# 11-DisplayPort.net
KiCad netlist of a schematic drawn in Altium Designer
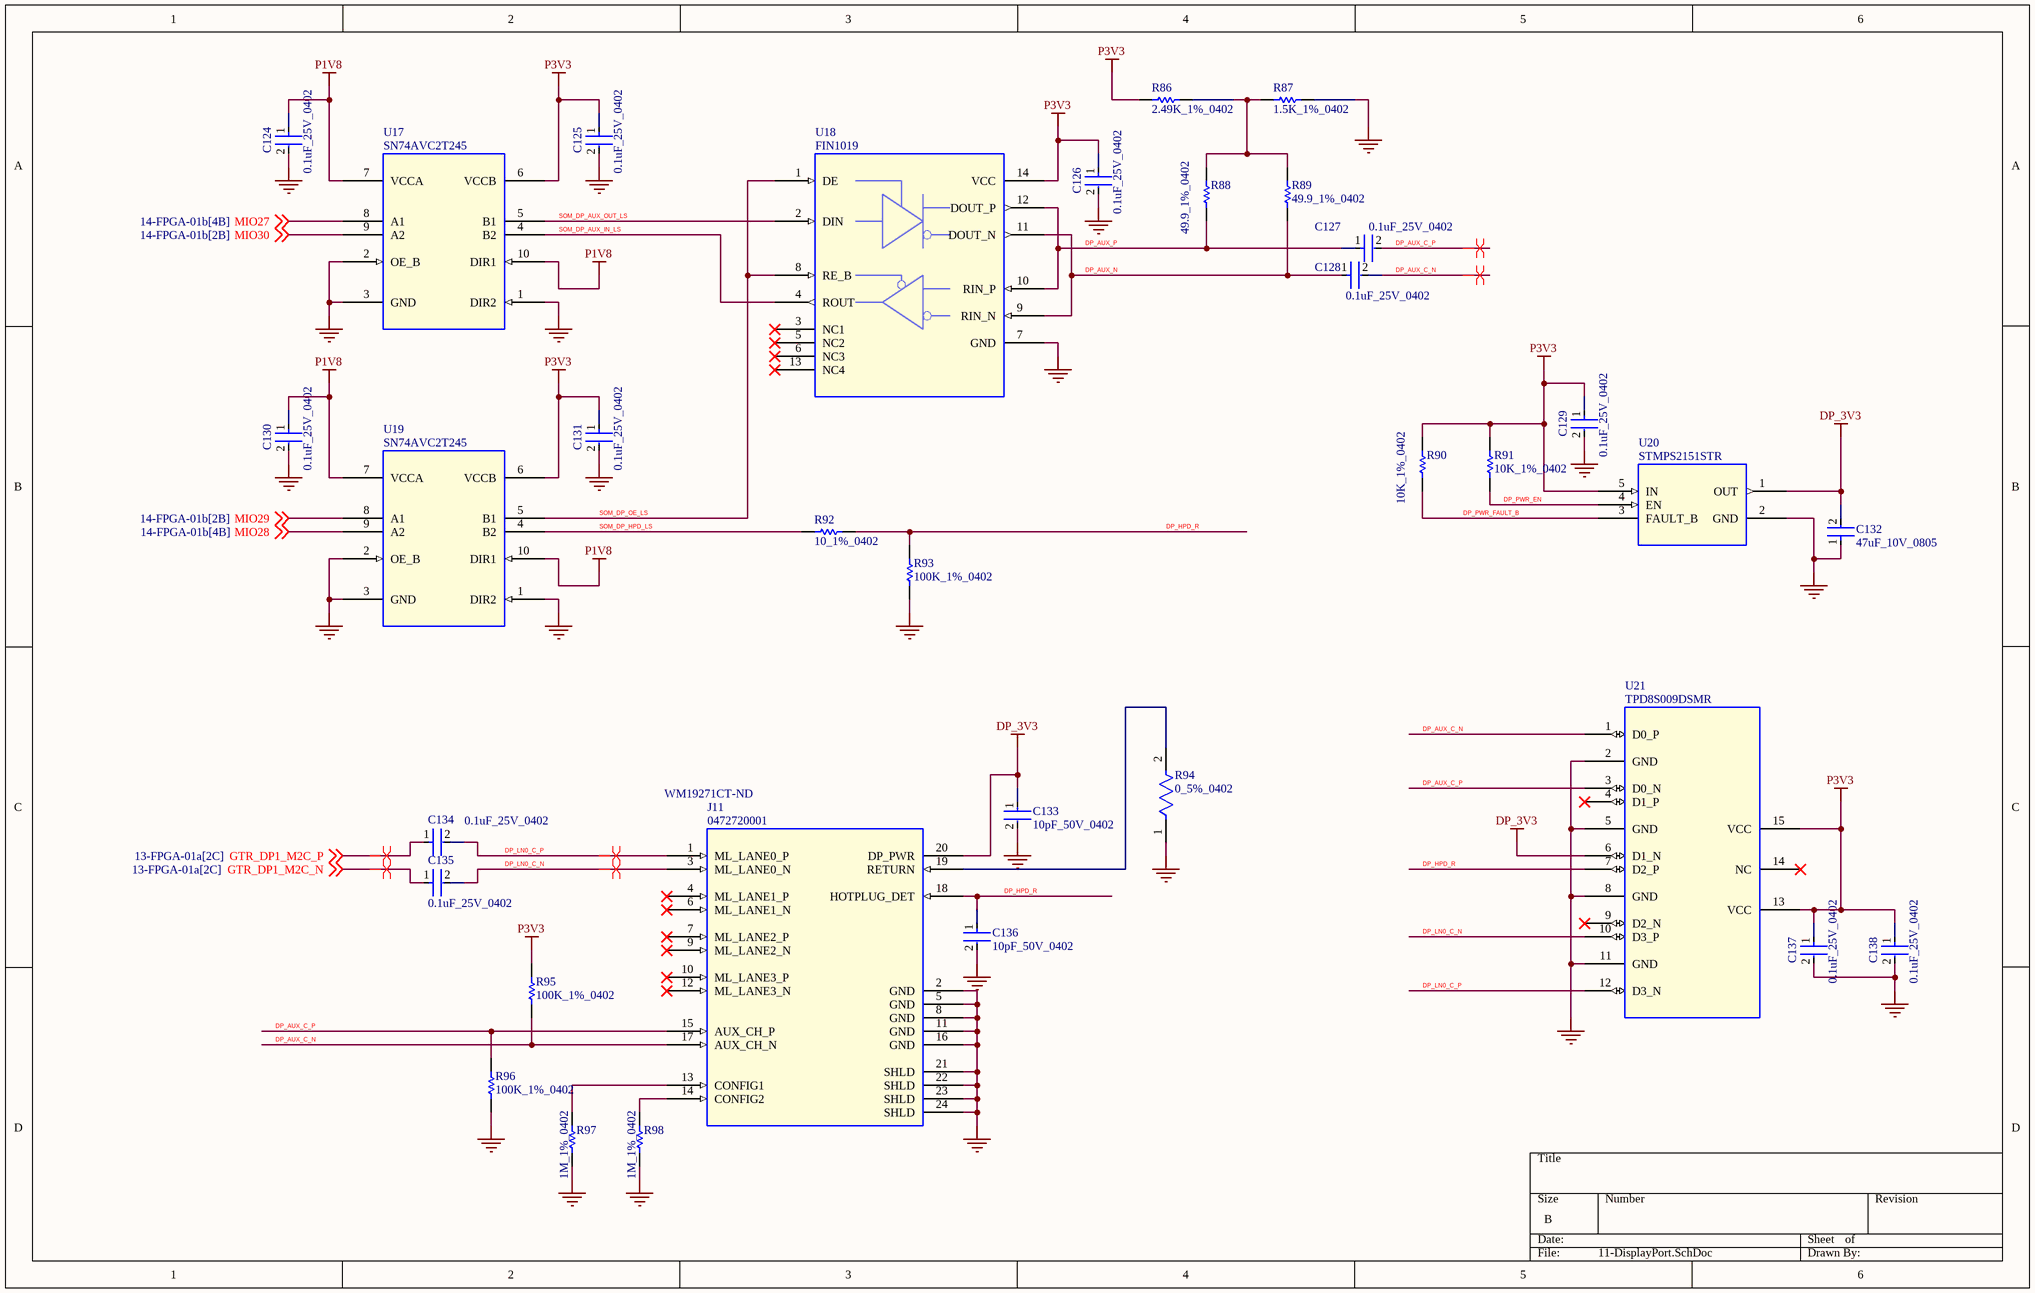
[diagram p0: 11-DisplayPort.SchDoc]

(export (version "E")
  (design (tool "Eeschema 10.0.6"))
  (components
    (comp (ref "C124")
      (value "0.1uF_25V_0402")
      (footprint "FP-0402-L_1_0_1-W_0_5_0_1-IPC_C")
      (description "General Purpose Ceramic Capacitor, 0402, 100nF, 10%, X7R, 15%, 25V")
      (fields (field (name "VOLTAGE") "25V") (field (name "TOLERANCE") "10%"))
      (libsource (lib "Altium Content Vault") (part "b4654b650e69147ec39a6b967a45e02"))
    )
    (comp (ref "C125")
      (value "0.1uF_25V_0402")
      (footprint "FP-0402-L_1_0_1-W_0_5_0_1-IPC_C")
      (description "General Purpose Ceramic Capacitor, 0402, 100nF, 10%, X7R, 15%, 25V")
      (fields (field (name "VOLTAGE") "25V") (field (name "TOLERANCE") "10%"))
      (libsource (lib "Altium Content Vault") (part "b4654b650e69147ec39a6b967a45e02"))
    )
    (comp (ref "C126")
      (value "0.1uF_25V_0402")
      (footprint "FP-0402-L_1_0_1-W_0_5_0_1-IPC_C")
      (description "General Purpose Ceramic Capacitor, 0402, 100nF, 10%, X7R, 15%, 25V")
      (fields (field (name "VOLTAGE") "25V") (field (name "TOLERANCE") "10%"))
      (libsource (lib "Altium Content Vault") (part "b4654b650e69147ec39a6b967a45e02"))
    )
    (comp (ref "C127")
      (value "0.1uF_25V_0402")
      (footprint "FP-0402-L_1_0_1-W_0_5_0_1-IPC_C")
      (description "General Purpose Ceramic Capacitor, 0402, 100nF, 10%, X7R, 15%, 25V")
      (fields (field (name "VOLTAGE") "25V") (field (name "TOLERANCE") "10%"))
      (libsource (lib "Altium Content Vault") (part "b4654b650e69147ec39a6b967a45e02"))
    )
    (comp (ref "C128")
      (value "0.1uF_25V_0402")
      (footprint "FP-0402-L_1_0_1-W_0_5_0_1-IPC_C")
      (description "General Purpose Ceramic Capacitor, 0402, 100nF, 10%, X7R, 15%, 25V")
      (fields (field (name "VOLTAGE") "25V") (field (name "TOLERANCE") "10%"))
      (libsource (lib "Altium Content Vault") (part "b4654b650e69147ec39a6b967a45e02"))
    )
    (comp (ref "C129")
      (value "0.1uF_25V_0402")
      (footprint "FP-0402-L_1_0_1-W_0_5_0_1-IPC_C")
      (description "General Purpose Ceramic Capacitor, 0402, 100nF, 10%, X7R, 15%, 25V")
      (fields (field (name "VOLTAGE") "25V") (field (name "TOLERANCE") "10%"))
      (libsource (lib "Altium Content Vault") (part "b4654b650e69147ec39a6b967a45e02"))
    )
    (comp (ref "C130")
      (value "0.1uF_25V_0402")
      (footprint "FP-0402-L_1_0_1-W_0_5_0_1-IPC_C")
      (description "General Purpose Ceramic Capacitor, 0402, 100nF, 10%, X7R, 15%, 25V")
      (fields (field (name "VOLTAGE") "25V") (field (name "TOLERANCE") "10%"))
      (libsource (lib "Altium Content Vault") (part "b4654b650e69147ec39a6b967a45e02"))
    )
    (comp (ref "C131")
      (value "0.1uF_25V_0402")
      (footprint "FP-0402-L_1_0_1-W_0_5_0_1-IPC_C")
      (description "General Purpose Ceramic Capacitor, 0402, 100nF, 10%, X7R, 15%, 25V")
      (fields (field (name "VOLTAGE") "25V") (field (name "TOLERANCE") "10%"))
      (libsource (lib "Altium Content Vault") (part "b4654b650e69147ec39a6b967a45e02"))
    )
    (comp (ref "C132")
      (value "47uF_10V_0805")
      (footprint "FP-GRM21B-0_2-e0_2_0_7-IPC_A")
      (description "Chip Multilayer Ceramic Capacitors for General Purpose, 0805, 47uF, X5R, 15%, 20%, 10V")
      (fields (field (name "TOLERANCE") "20%") (field (name "VOLTAGE") "10V"))
      (libsource (lib "Altium Content Vault") (part "b4654b650e69147ec39a6b967a45e02"))
    )
    (comp (ref "C133")
      (value "10pF_50V_0402")
      (footprint "FP-C1005-050-0_05-IPC_C")
      (description "CAP CER 10PF 50V C0G 0402")
      (fields (field (name "VOLTAGE") "50V"))
      (libsource (lib "Altium Content Vault") (part "b4654b650e69147ec39a6b967a45e02"))
    )
    (comp (ref "C134")
      (value "0.1uF_25V_0402")
      (footprint "FP-0402-L_1_0_1-W_0_5_0_1-IPC_C")
      (description "General Purpose Ceramic Capacitor, 0402, 100nF, 10%, X7R, 15%, 25V")
      (fields (field (name "VOLTAGE") "25V") (field (name "TOLERANCE") "10%"))
      (libsource (lib "Altium Content Vault") (part "b4654b650e69147ec39a6b967a45e02"))
    )
    (comp (ref "C135")
      (value "0.1uF_25V_0402")
      (footprint "FP-0402-L_1_0_1-W_0_5_0_1-IPC_C")
      (description "General Purpose Ceramic Capacitor, 0402, 100nF, 10%, X7R, 15%, 25V")
      (fields (field (name "VOLTAGE") "25V") (field (name "TOLERANCE") "10%"))
      (libsource (lib "Altium Content Vault") (part "b4654b650e69147ec39a6b967a45e02"))
    )
    (comp (ref "C136")
      (value "10pF_50V_0402")
      (footprint "FP-C1005-050-0_05-IPC_C")
      (description "CAP CER 10PF 50V C0G 0402")
      (fields (field (name "VOLTAGE") "50V"))
      (libsource (lib "Altium Content Vault") (part "b4654b650e69147ec39a6b967a45e02"))
    )
    (comp (ref "C137")
      (value "0.1uF_25V_0402")
      (footprint "FP-0402-L_1_0_1-W_0_5_0_1-IPC_C")
      (description "General Purpose Ceramic Capacitor, 0402, 100nF, 10%, X7R, 15%, 25V")
      (fields (field (name "VOLTAGE") "25V") (field (name "TOLERANCE") "10%"))
      (libsource (lib "Altium Content Vault") (part "b4654b650e69147ec39a6b967a45e02"))
    )
    (comp (ref "C138")
      (value "0.1uF_25V_0402")
      (footprint "FP-0402-L_1_0_1-W_0_5_0_1-IPC_C")
      (description "General Purpose Ceramic Capacitor, 0402, 100nF, 10%, X7R, 15%, 25V")
      (fields (field (name "VOLTAGE") "25V") (field (name "TOLERANCE") "10%"))
      (libsource (lib "Altium Content Vault") (part "b4654b650e69147ec39a6b967a45e02"))
    )
    (comp (ref "J11")
      (value "0472720001")
      (footprint "CON_MOLEX_47272")
      (description "Conn Rcpt DisplayPort Female RA 20 Pos 0.5mm P Black SMT")
      (fields
        (field (name "AGILE PART NUMBER") "CON-00139-01")
        (field (name "MANUFACTURER") "MOLEX")
        (field (name "SUPPLIER PART NUMBER 1") "WM19271CT-ND")
      )
      (libsource (lib "*") (part "0472720001"))
    )
    (comp (ref "R86")
      (value "2.49K_1%_0402")
      (footprint "RESC1005X40X25ML05T05")
      (fields (field (name "MANUFACTURER") "Vishay Dale") (field (name "PART NUMBER") "CRCW04022K49FKTD"))
      (libsource (lib "Altium Content Vault") (part "RES"))
    )
    (comp (ref "R87")
      (value "1.5K_1%_0402")
      (footprint "RESC1005X40X25NL05T05")
      (fields (field (name "PART NUMBER") "CRCW04021K50FKED") (field (name "MANUFACTURER") "Vishay Dale"))
      (libsource (lib "Altium Content Vault") (part "RES"))
    )
    (comp (ref "R88")
      (value "49.9_1%_0402")
      (footprint "RESC1005X40X25NL10T10")
      (fields (field (name "PART NUMBER") "RK73H1ETTP49R9F") (field (name "MANUFACTURER") "KOA Speer"))
      (libsource (lib "Altium Content Vault") (part "RES"))
    )
    (comp (ref "R89")
      (value "49.9_1%_0402")
      (footprint "RESC1005X40X25NL10T10")
      (fields (field (name "PART NUMBER") "RK73H1ETTP49R9F") (field (name "MANUFACTURER") "KOA Speer"))
      (libsource (lib "Altium Content Vault") (part "RES"))
    )
    (comp (ref "R90")
      (value "10K_1%_0402")
      (footprint "RESC1005X40X25ML05T05")
      (fields (field (name "PART NUMBER") "ERJ-2GEJ103X") (field (name "MANUFACTURER") "Panasonic"))
      (libsource (lib "Altium Content Vault") (part "RES"))
    )
    (comp (ref "R91")
      (value "10K_1%_0402")
      (footprint "RESC1005X40X25ML05T05")
      (fields (field (name "PART NUMBER") "ERJ-2GEJ103X") (field (name "MANUFACTURER") "Panasonic"))
      (libsource (lib "Altium Content Vault") (part "RES"))
    )
    (comp (ref "R92")
      (value "10_1%_0402")
      (footprint "RESC1005X40X25LL10T10")
      (fields (field (name "PART NUMBER") "RK73H1ETTP10R0F") (field (name "MANUFACTURER") "KOA Speer"))
      (libsource (lib "Altium Content Vault") (part "RES"))
    )
    (comp (ref "R93")
      (value "100K_1%_0402")
      (footprint "RESC1005X40X25ML05T05")
      (fields (field (name "PART NUMBER") "CRCW0402100KFKTD") (field (name "MANUFACTURER") "Vishay Dale"))
      (libsource (lib "Altium Content Vault") (part "RES"))
    )
    (comp (ref "R94")
      (value "0_5%_0402")
      (footprint "FP-AC0402-0_37-IPC_B")
      (description "RESISTOR 0402 JUMPER ZERO OHM")
      (fields (field (name "TOLERANCE") "1%"))
      (libsource (lib "Altium Content Vault") (part "1029c3af85768c4190bb7ad29bc67b5"))
    )
    (comp (ref "R95")
      (value "100K_1%_0402")
      (footprint "RESC1005X40X25ML05T05")
      (fields (field (name "PART NUMBER") "CRCW0402100KFKTD") (field (name "MANUFACTURER") "Vishay Dale"))
      (libsource (lib "Altium Content Vault") (part "RES"))
    )
    (comp (ref "R96")
      (value "100K_1%_0402")
      (footprint "RESC1005X40X25ML05T05")
      (fields (field (name "PART NUMBER") "CRCW0402100KFKTD") (field (name "MANUFACTURER") "Vishay Dale"))
      (libsource (lib "Altium Content Vault") (part "RES"))
    )
    (comp (ref "R97")
      (value "1M_1%_0402")
      (footprint "RESC1005X40X25NL10T10")
      (fields
        (field (name "MANUFACTURER") "TE Connectivity / AMP")
        (field (name "PART NUMBER") "CRG0402F1M0")
      )
      (libsource (lib "Altium Content Vault") (part "RES"))
    )
    (comp (ref "R98")
      (value "1M_1%_0402")
      (footprint "RESC1005X40X25NL10T10")
      (fields
        (field (name "MANUFACTURER") "TE Connectivity / AMP")
        (field (name "PART NUMBER") "CRG0402F1M0")
      )
      (libsource (lib "Altium Content Vault") (part "RES"))
    )
    (comp (ref "U17")
      (value "SN74AVC2T245")
      (footprint "QFN40P140X180X55-10")
      (description "IC Lvl Trans 2-Bit Bidir 500Mbps 1.2-3.6V 50mA UQFN-10")
      (fields
        (field (name "AGILE PART NUMBER") "ICS-00048-01")
        (field (name "MANUFACTURER") "TEXAS INSTRUMENTS")
      )
      (libsource (lib "*") (part "SN74AVC2T245"))
    )
    (comp (ref "U18")
      (value "FIN1019")
      (footprint "TSSOP_14")
      (description "IC Lvl Trans LVTTL-LVDS Diff 400Mbps 3.3V 2.5nSec TSSOP-14")
      (fields (field (name "AGILE PART NUMBER") "ICS-00279-01") (field (name "MANUFACTURER") "FAIRCHILD"))
      (libsource (lib "*") (part "FIN1019"))
    )
    (comp (ref "U19")
      (value "SN74AVC2T245")
      (footprint "QFN40P140X180X55-10")
      (description "IC Lvl Trans 2-Bit Bidir 500Mbps 1.2-3.6V 50mA UQFN-10")
      (fields
        (field (name "AGILE PART NUMBER") "ICS-00048-01")
        (field (name "MANUFACTURER") "TEXAS INSTRUMENTS")
      )
      (libsource (lib "*") (part "SN74AVC2T245"))
    )
    (comp (ref "U20")
      (value "STMPS2151STR")
      (footprint "SOT95P280X145_5")
      (description "IC Switch Power 500mA 2.7-5.5V 110mR SOT23-5")
      (fields
        (field (name "AGILE PART NUMBER") "ICS-00662-01")
        (field (name "MANUFACTURER") "STMicroelectronics")
      )
      (libsource (lib "*") (part "STMPS2151"))
    )
    (comp (ref "U21")
      (value "TPD8S009DSMR")
      (footprint "SON_15P")
      (description "TVSD 8-Ch 5.5V 2.5A 25W 4GHz SON-15 8KV Contact Discharge")
      (fields
        (field (name "AGILE PART NUMBER") "ICS-00196-01")
        (field (name "MANUFACTURER") "TEXAS INSTRUMENTS")
      )
      (libsource (lib "*") (part "TPD8S009DSMR"))
    )
  )
  (nets
    (net (code "1") (name "/DP_AUX_C_N") (class "Default")
      (node (ref "C128") (pin "2") (pinfunction "2_2") (pintype "passive"))
      (node (ref "J11") (pin "17") (pinfunction "AUX_CH_N_17") (pintype "input"))
      (node (ref "R95") (pin "1") (pinfunction "1_1") (pintype "passive"))
      (node (ref "U21") (pin "1") (pinfunction "D0_P_1") (pintype "bidirectional"))
    )
    (net (code "2") (name "/DP_AUX_C_P") (class "Default")
      (node (ref "C127") (pin "2") (pinfunction "2_2") (pintype "passive"))
      (node (ref "J11") (pin "15") (pinfunction "AUX_CH_P_15") (pintype "input"))
      (node (ref "R96") (pin "2") (pinfunction "2_2") (pintype "passive"))
      (node (ref "U21") (pin "3") (pinfunction "D0_N_3") (pintype "bidirectional"))
    )
    (net (code "3") (name "/DP_AUX_N") (class "Default")
      (node (ref "C128") (pin "1") (pinfunction "1_1") (pintype "passive"))
      (node (ref "R89") (pin "1") (pinfunction "1_1") (pintype "passive"))
      (node (ref "U18") (pin "11") (pinfunction "DOUT_N_11") (pintype "output"))
      (node (ref "U18") (pin "9") (pinfunction "RIN_N_9") (pintype "input"))
    )
    (net (code "4") (name "/DP_AUX_P") (class "Default")
      (node (ref "C127") (pin "1") (pinfunction "1_1") (pintype "passive"))
      (node (ref "R88") (pin "1") (pinfunction "1_1") (pintype "passive"))
      (node (ref "U18") (pin "10") (pinfunction "RIN_P_10") (pintype "input"))
      (node (ref "U18") (pin "12") (pinfunction "DOUT_P_12") (pintype "output"))
    )
    (net (code "5") (name "/DP_HPD_R") (class "Default")
      (node (ref "C136") (pin "1") (pinfunction "1_1") (pintype "passive"))
      (node (ref "J11") (pin "18") (pinfunction "HOTPLUG_DET_18") (pintype "input"))
      (node (ref "R92") (pin "2") (pinfunction "2_2") (pintype "passive"))
      (node (ref "R93") (pin "1") (pinfunction "1_1") (pintype "passive"))
      (node (ref "U21") (pin "7") (pinfunction "D2_P_7") (pintype "bidirectional"))
    )
    (net (code "6") (name "/DP_LN0_C_N") (class "Default")
      (node (ref "C135") (pin "2") (pinfunction "2_2") (pintype "passive"))
      (node (ref "J11") (pin "3") (pinfunction "ML_LANE0_N_3") (pintype "input"))
      (node (ref "U21") (pin "10") (pinfunction "D3_P_10") (pintype "bidirectional"))
    )
    (net (code "7") (name "/DP_LN0_C_P") (class "Default")
      (node (ref "C134") (pin "2") (pinfunction "2_2") (pintype "passive"))
      (node (ref "J11") (pin "1") (pinfunction "ML_LANE0_P_1") (pintype "input"))
      (node (ref "U21") (pin "12") (pinfunction "D3_N_12") (pintype "bidirectional"))
    )
    (net (code "8") (name "/DP_PWR_EN") (class "Default")
      (node (ref "R91") (pin "2") (pinfunction "2_2") (pintype "passive"))
      (node (ref "U20") (pin "4") (pinfunction "EN_4") (pintype "input"))
    )
    (net (code "9") (name "/DP_PWR_FAULT_B") (class "Default")
      (node (ref "R90") (pin "1") (pinfunction "1_1") (pintype "passive"))
      (node (ref "U20") (pin "3") (pinfunction "FAULT_B_3") (pintype "open_collector"))
    )
    (net (code "10") (name "/SOM_DP_AUX_IN_LS") (class "Default")
      (node (ref "U17") (pin "4") (pinfunction "B2_4") (pintype "passive"))
      (node (ref "U18") (pin "4") (pinfunction "ROUT_4") (pintype "output"))
    )
    (net (code "11") (name "/SOM_DP_AUX_OUT_LS") (class "Default")
      (node (ref "U17") (pin "5") (pinfunction "B1_5") (pintype "passive"))
      (node (ref "U18") (pin "2") (pinfunction "DIN_2") (pintype "input"))
    )
    (net (code "12") (name "/SOM_DP_HPD_LS") (class "Default")
      (node (ref "R92") (pin "1") (pinfunction "1_1") (pintype "passive"))
      (node (ref "U19") (pin "4") (pinfunction "B2_4") (pintype "passive"))
    )
    (net (code "13") (name "/SOM_DP_OE_LS") (class "Default")
      (node (ref "U18") (pin "1") (pinfunction "DE_1") (pintype "input"))
      (node (ref "U18") (pin "8") (pinfunction "RE_B_8") (pintype "input"))
      (node (ref "U19") (pin "5") (pinfunction "B1_5") (pintype "passive"))
    )
    (net (code "14") (name "DP_3V3") (class "Default")
      (node (ref "C132") (pin "2") (pinfunction "2_2") (pintype "passive"))
      (node (ref "C133") (pin "1") (pinfunction "1_1") (pintype "passive"))
      (node (ref "J11") (pin "20") (pinfunction "DP_PWR_20") (pintype "power_in"))
      (node (ref "U20") (pin "1") (pinfunction "OUT_1") (pintype "output"))
      (node (ref "U21") (pin "6") (pinfunction "D1_N_6") (pintype "bidirectional"))
    )
    (net (code "15") (name "GND") (class "Default")
      (node (ref "C124") (pin "2") (pinfunction "2_2") (pintype "passive"))
      (node (ref "C125") (pin "2") (pinfunction "2_2") (pintype "passive"))
      (node (ref "C126") (pin "2") (pinfunction "2_2") (pintype "passive"))
      (node (ref "C129") (pin "2") (pinfunction "2_2") (pintype "passive"))
      (node (ref "C130") (pin "2") (pinfunction "2_2") (pintype "passive"))
      (node (ref "C131") (pin "2") (pinfunction "2_2") (pintype "passive"))
      (node (ref "C132") (pin "1") (pinfunction "1_1") (pintype "passive"))
      (node (ref "C133") (pin "2") (pinfunction "2_2") (pintype "passive"))
      (node (ref "C136") (pin "2") (pinfunction "2_2") (pintype "passive"))
      (node (ref "C137") (pin "2") (pinfunction "2_2") (pintype "passive"))
      (node (ref "C138") (pin "2") (pinfunction "2_2") (pintype "passive"))
      (node (ref "J11") (pin "11") (pinfunction "GND_11") (pintype "power_in"))
      (node (ref "J11") (pin "16") (pinfunction "GND_16") (pintype "power_in"))
      (node (ref "J11") (pin "2") (pinfunction "GND_2") (pintype "power_in"))
      (node (ref "J11") (pin "21") (pinfunction "SHLD_21") (pintype "power_in"))
      (node (ref "J11") (pin "22") (pinfunction "SHLD_22") (pintype "power_in"))
      (node (ref "J11") (pin "23") (pinfunction "SHLD_23") (pintype "power_in"))
      (node (ref "J11") (pin "24") (pinfunction "SHLD_24") (pintype "power_in"))
      (node (ref "J11") (pin "5") (pinfunction "GND_5") (pintype "power_in"))
      (node (ref "J11") (pin "8") (pinfunction "GND_8") (pintype "power_in"))
      (node (ref "R87") (pin "2") (pinfunction "2_2") (pintype "passive"))
      (node (ref "R93") (pin "2") (pinfunction "2_2") (pintype "passive"))
      (node (ref "R94") (pin "1") (pinfunction "1_1") (pintype "passive"))
      (node (ref "R96") (pin "1") (pinfunction "1_1") (pintype "passive"))
      (node (ref "R97") (pin "1") (pinfunction "1_1") (pintype "passive"))
      (node (ref "R98") (pin "1") (pinfunction "1_1") (pintype "passive"))
      (node (ref "U17") (pin "1") (pinfunction "DIR2_1") (pintype "input"))
      (node (ref "U17") (pin "2") (pinfunction "OE_B_2") (pintype "input"))
      (node (ref "U17") (pin "3") (pinfunction "GND_3") (pintype "power_in"))
      (node (ref "U18") (pin "7") (pinfunction "GND_7") (pintype "power_in"))
      (node (ref "U19") (pin "1") (pinfunction "DIR2_1") (pintype "input"))
      (node (ref "U19") (pin "2") (pinfunction "OE_B_2") (pintype "input"))
      (node (ref "U19") (pin "3") (pinfunction "GND_3") (pintype "power_in"))
      (node (ref "U20") (pin "2") (pinfunction "GND_2") (pintype "power_in"))
      (node (ref "U21") (pin "11") (pinfunction "GND_11") (pintype "power_in"))
      (node (ref "U21") (pin "2") (pinfunction "GND_2") (pintype "power_in"))
      (node (ref "U21") (pin "5") (pinfunction "GND_5") (pintype "power_in"))
      (node (ref "U21") (pin "8") (pinfunction "GND_8") (pintype "power_in"))
    )
    (net (code "16") (name "GTR_DP1_M2C_N") (class "Default")
      (node (ref "C135") (pin "1") (pinfunction "1_1") (pintype "passive"))
    )
    (net (code "17") (name "GTR_DP1_M2C_P") (class "Default")
      (node (ref "C134") (pin "1") (pinfunction "1_1") (pintype "passive"))
    )
    (net (code "18") (name "MIO27") (class "Default")
      (node (ref "U17") (pin "8") (pinfunction "A1_8") (pintype "passive"))
    )
    (net (code "19") (name "MIO28") (class "Default")
      (node (ref "U19") (pin "9") (pinfunction "A2_9") (pintype "passive"))
    )
    (net (code "20") (name "MIO29") (class "Default")
      (node (ref "U19") (pin "8") (pinfunction "A1_8") (pintype "passive"))
    )
    (net (code "21") (name "MIO30") (class "Default")
      (node (ref "U17") (pin "9") (pinfunction "A2_9") (pintype "passive"))
    )
    (net (code "22") (name "Net-(J11-CONFIG1)") (class "Default")
      (node (ref "J11") (pin "13") (pinfunction "CONFIG1_13") (pintype "input"))
      (node (ref "R97") (pin "2") (pinfunction "2_2") (pintype "passive"))
    )
    (net (code "23") (name "Net-(J11-CONFIG2)") (class "Default")
      (node (ref "J11") (pin "14") (pinfunction "CONFIG2_14") (pintype "input"))
      (node (ref "R98") (pin "2") (pinfunction "2_2") (pintype "passive"))
    )
    (net (code "24") (name "Net-(J11-RETURN)") (class "Default")
      (node (ref "J11") (pin "19") (pinfunction "RETURN_19") (pintype "input"))
      (node (ref "R94") (pin "2") (pinfunction "2_2") (pintype "passive"))
    )
    (net (code "25") (name "Net-(R86-Pad2)") (class "Default")
      (node (ref "R86") (pin "2") (pinfunction "2_2") (pintype "passive"))
      (node (ref "R87") (pin "1") (pinfunction "1_1") (pintype "passive"))
      (node (ref "R88") (pin "2") (pinfunction "2_2") (pintype "passive"))
      (node (ref "R89") (pin "2") (pinfunction "2_2") (pintype "passive"))
    )
    (net (code "26") (name "P1V8") (class "Default")
      (node (ref "C124") (pin "1") (pinfunction "1_1") (pintype "passive"))
      (node (ref "C130") (pin "1") (pinfunction "1_1") (pintype "passive"))
      (node (ref "U17") (pin "10") (pinfunction "DIR1_10") (pintype "input"))
      (node (ref "U17") (pin "7") (pinfunction "VCCA_7") (pintype "power_in"))
      (node (ref "U19") (pin "10") (pinfunction "DIR1_10") (pintype "input"))
      (node (ref "U19") (pin "7") (pinfunction "VCCA_7") (pintype "power_in"))
    )
    (net (code "27") (name "P3V3") (class "Default")
      (node (ref "C125") (pin "1") (pinfunction "1_1") (pintype "passive"))
      (node (ref "C126") (pin "1") (pinfunction "1_1") (pintype "passive"))
      (node (ref "C129") (pin "1") (pinfunction "1_1") (pintype "passive"))
      (node (ref "C131") (pin "1") (pinfunction "1_1") (pintype "passive"))
      (node (ref "C137") (pin "1") (pinfunction "1_1") (pintype "passive"))
      (node (ref "C138") (pin "1") (pinfunction "1_1") (pintype "passive"))
      (node (ref "R86") (pin "1") (pinfunction "1_1") (pintype "passive"))
      (node (ref "R90") (pin "2") (pinfunction "2_2") (pintype "passive"))
      (node (ref "R91") (pin "1") (pinfunction "1_1") (pintype "passive"))
      (node (ref "R95") (pin "2") (pinfunction "2_2") (pintype "passive"))
      (node (ref "U17") (pin "6") (pinfunction "VCCB_6") (pintype "power_in"))
      (node (ref "U18") (pin "14") (pinfunction "VCC_14") (pintype "power_in"))
      (node (ref "U19") (pin "6") (pinfunction "VCCB_6") (pintype "power_in"))
      (node (ref "U20") (pin "5") (pinfunction "IN_5") (pintype "input"))
      (node (ref "U21") (pin "13") (pinfunction "VCC_13") (pintype "power_in"))
      (node (ref "U21") (pin "15") (pinfunction "VCC_15") (pintype "power_in"))
    )
    (net (code "28") (name "unconnected-(J11-ML_LANE1_N-Pad6)") (class "Default")
      (node (ref "J11") (pin "6") (pinfunction "ML_LANE1_N_6") (pintype "input+no_connect"))
    )
    (net (code "29") (name "unconnected-(J11-ML_LANE1_P-Pad4)") (class "Default")
      (node (ref "J11") (pin "4") (pinfunction "ML_LANE1_P_4") (pintype "input+no_connect"))
    )
    (net (code "30") (name "unconnected-(J11-ML_LANE2_N-Pad9)") (class "Default")
      (node (ref "J11") (pin "9") (pinfunction "ML_LANE2_N_9") (pintype "input+no_connect"))
    )
    (net (code "31") (name "unconnected-(J11-ML_LANE2_P-Pad7)") (class "Default")
      (node (ref "J11") (pin "7") (pinfunction "ML_LANE2_P_7") (pintype "input+no_connect"))
    )
    (net (code "32") (name "unconnected-(J11-ML_LANE3_N-Pad12)") (class "Default")
      (node (ref "J11") (pin "12") (pinfunction "ML_LANE3_N_12") (pintype "input+no_connect"))
    )
    (net (code "33") (name "unconnected-(J11-ML_LANE3_P-Pad10)") (class "Default")
      (node (ref "J11") (pin "10") (pinfunction "ML_LANE3_P_10") (pintype "input+no_connect"))
    )
    (net (code "34") (name "unconnected-(U18-NC1-Pad3)") (class "Default")
      (node (ref "U18") (pin "3") (pinfunction "NC1_3") (pintype "passive+no_connect"))
    )
    (net (code "35") (name "unconnected-(U18-NC2-Pad5)") (class "Default")
      (node (ref "U18") (pin "5") (pinfunction "NC2_5") (pintype "passive+no_connect"))
    )
    (net (code "36") (name "unconnected-(U18-NC3-Pad6)") (class "Default")
      (node (ref "U18") (pin "6") (pinfunction "NC3_6") (pintype "passive+no_connect"))
    )
    (net (code "37") (name "unconnected-(U18-NC4-Pad13)") (class "Default")
      (node (ref "U18") (pin "13") (pinfunction "NC4_13") (pintype "passive+no_connect"))
    )
    (net (code "38") (name "unconnected-(U21-D1_P-Pad4)") (class "Default")
      (node (ref "U21") (pin "4") (pinfunction "D1_P_4") (pintype "bidirectional+no_connect"))
    )
    (net (code "39") (name "unconnected-(U21-D2_N-Pad9)") (class "Default")
      (node (ref "U21") (pin "9") (pinfunction "D2_N_9") (pintype "bidirectional+no_connect"))
    )
    (net (code "40") (name "unconnected-(U21-NC-Pad14)") (class "Default")
      (node (ref "U21") (pin "14") (pinfunction "NC_14") (pintype "passive+no_connect"))
    )
  )
)
